# BBB-Supply.net
KiCad netlist of a schematic drawn in Altium Designer
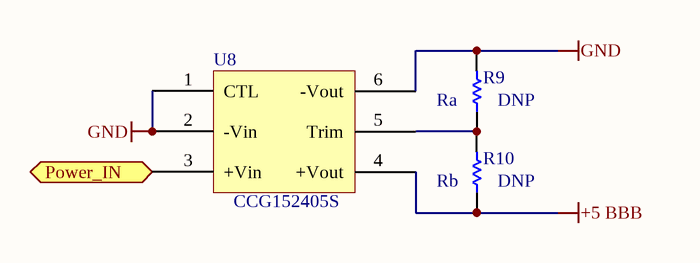
[diagram p0: BBB-Supply.SchDoc]

(export (version "E")
  (design (tool "Eeschema 10.0.6"))
  (components
    (comp (ref "R9")
      (value "DNP")
      (footprint "RESC0805(2012)_M")
      (description "Vout = 12.05 ­ (445.7 / 63.1+Ra)")
      (libsource (lib "Altium Content Vault") (part "CMP-1013-00017-1"))
    )
    (comp (ref "R10")
      (value "DNP")
      (footprint "RESC0805(2012)_M")
      (description "Vout = 12.05 + (50.96 / 22+Rb)")
      (libsource (lib "Altium Content Vault") (part "CMP-1013-00017-1"))
    )
    (comp (ref "U8")
      (value "CCG152405S")
      (footprint "PXB15-24WS05/NT")
      (description "DC DC CONVERTER 5V 15W")
      (fields (field (name "MANUFACTURER") "TDK-Lambda Americas Inc."))
      (libsource (lib "ZLS_Schematic_lib") (part "PXB15-24WS05/NT"))
    )
  )
  (nets
    (net (code "1") (name "+5 BBB") (class "Default")
      (node (ref "R10") (pin "1") (pinfunction "1_1") (pintype "passive"))
      (node (ref "U8") (pin "4") (pinfunction "+Vout_4") (pintype "passive"))
    )
    (net (code "2") (name "/Power_IN") (class "Default")
      (node (ref "U8") (pin "3") (pinfunction "+Vin_3") (pintype "passive"))
    )
    (net (code "3") (name "GND") (class "Default")
      (node (ref "R9") (pin "2") (pinfunction "2_2") (pintype "passive"))
      (node (ref "U8") (pin "1") (pinfunction "CTL_1") (pintype "passive"))
      (node (ref "U8") (pin "2") (pinfunction "-Vin_2") (pintype "passive"))
      (node (ref "U8") (pin "6") (pinfunction "-Vout_6") (pintype "passive"))
    )
    (net (code "4") (name "Net-(U8-Trim)") (class "Default")
      (node (ref "R10") (pin "2") (pinfunction "2_2") (pintype "passive"))
      (node (ref "R9") (pin "1") (pinfunction "1_1") (pintype "passive"))
      (node (ref "U8") (pin "5") (pinfunction "Trim_5") (pintype "passive"))
    )
  )
)
